# dial-a-hue.net
KiCad netlist of a schematic drawn in EAGLE
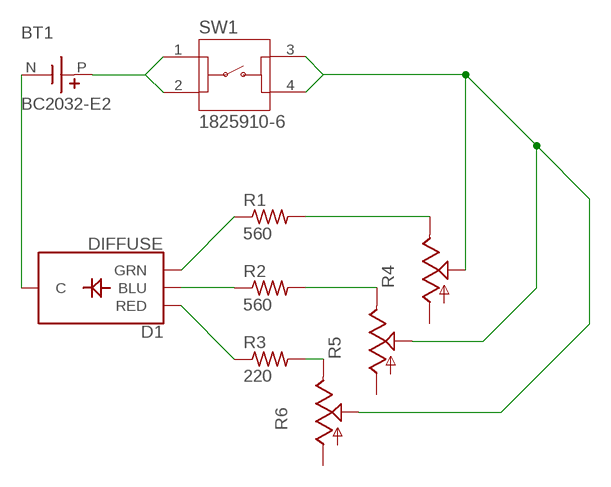
[diagram p0: schematic, sheet 1]

(export (version "E")
  (design (tool "Eeschema 10.0.6"))
  (components
    (comp (ref "BT1")
      (value "BC2032-E2")
      (footprint "eagle-import:MPD_BC2032-E2")
      (fields (field (name "DIGI-KEY_PART_NUMBER") "BC2032-E2-ND") (field (name "MF") "MPD _Memory"))
      (libsource (lib "eagle-import") (part "BC2032-E2"))
    )
    (comp (ref "D1")
      (value "DIFFUSE")
      (footprint "eagle-import:LED-RGB-THRU")
      (libsource (lib "eagle-import") (part "LED-RGB-CCDIFFUSE"))
    )
    (comp (ref "R1")
      (value "560")
      (footprint "eagle-import:0207_10")
      (libsource (lib "eagle-import") (part "R-US_0207/10"))
    )
    (comp (ref "R2")
      (value "560")
      (footprint "eagle-import:0207_10")
      (libsource (lib "eagle-import") (part "R-US_0207/10"))
    )
    (comp (ref "R3")
      (value "220")
      (footprint "eagle-import:0207_10")
      (libsource (lib "eagle-import") (part "R-US_0207/10"))
    )
    (comp (ref "R4")
      (value "TRIM_US-LI10")
      (footprint "eagle-import:LI10")
      (libsource (lib "eagle-import") (part "TRIM_US-LI10"))
    )
    (comp (ref "R5")
      (value "TRIM_US-LI10")
      (footprint "eagle-import:LI10")
      (libsource (lib "eagle-import") (part "TRIM_US-LI10"))
    )
    (comp (ref "R6")
      (value "TRIM_US-LI10")
      (footprint "eagle-import:LI10")
      (libsource (lib "eagle-import") (part "TRIM_US-LI10"))
    )
    (comp (ref "SW1")
      (value "1825910-6")
      (footprint "eagle-import:SW_1825910-6-4")
      (fields (field (name "DIGI-KEY_PART_NUMBER") "450-1650-ND") (field (name "MF") "TE Connectivity"))
      (libsource (lib "eagle-import") (part "1825910-6"))
    )
  )
  (nets
    (net (code "1") (name "Net-(BT1-PadP)") (class "Default")
      (node (ref "BT1") (pin "P") (pinfunction "P_P") (pintype "passive"))
      (node (ref "SW1") (pin "1") (pinfunction "1_1") (pintype "passive"))
      (node (ref "SW1") (pin "2") (pinfunction "2_2") (pintype "passive"))
    )
    (net (code "2") (name "Net-(D1-BLU)") (class "Default")
      (node (ref "D1") (pin "4") (pinfunction "BLU_4") (pintype "bidirectional"))
      (node (ref "R2") (pin "1") (pinfunction "1_1") (pintype "passive"))
    )
    (net (code "3") (name "Net-(D1-C)") (class "Default")
      (node (ref "BT1") (pin "N") (pinfunction "N_N") (pintype "passive"))
      (node (ref "D1") (pin "2") (pinfunction "C_2") (pintype "bidirectional"))
    )
    (net (code "4") (name "Net-(D1-GRN)") (class "Default")
      (node (ref "D1") (pin "3") (pinfunction "GRN_3") (pintype "bidirectional"))
      (node (ref "R1") (pin "1") (pinfunction "1_1") (pintype "passive"))
    )
    (net (code "5") (name "Net-(D1-RED)") (class "Default")
      (node (ref "D1") (pin "1") (pinfunction "RED_1") (pintype "bidirectional"))
      (node (ref "R3") (pin "1") (pinfunction "1_1") (pintype "passive"))
    )
    (net (code "6") (name "Net-(R1-Pad2)") (class "Default")
      (node (ref "R1") (pin "2") (pinfunction "2_2") (pintype "passive"))
      (node (ref "R4") (pin "E") (pinfunction "E_E") (pintype "passive"))
    )
    (net (code "7") (name "Net-(R2-Pad2)") (class "Default")
      (node (ref "R2") (pin "2") (pinfunction "2_2") (pintype "passive"))
      (node (ref "R5") (pin "E") (pinfunction "E_E") (pintype "passive"))
    )
    (net (code "8") (name "Net-(R3-Pad2)") (class "Default")
      (node (ref "R3") (pin "2") (pinfunction "2_2") (pintype "passive"))
      (node (ref "R6") (pin "E") (pinfunction "E_E") (pintype "passive"))
    )
    (net (code "9") (name "Net-(R4-PadS)") (class "Default")
      (node (ref "R4") (pin "S") (pinfunction "S_S") (pintype "passive"))
      (node (ref "R5") (pin "S") (pinfunction "S_S") (pintype "passive"))
      (node (ref "R6") (pin "S") (pinfunction "S_S") (pintype "passive"))
      (node (ref "SW1") (pin "3") (pinfunction "3_3") (pintype "passive"))
      (node (ref "SW1") (pin "4") (pinfunction "4_4") (pintype "passive"))
    )
    (net (code "10") (name "unconnected-(R4-PadA)") (class "Default")
      (node (ref "R4") (pin "A") (pinfunction "A_A") (pintype "passive"))
    )
    (net (code "11") (name "unconnected-(R5-PadA)") (class "Default")
      (node (ref "R5") (pin "A") (pinfunction "A_A") (pintype "passive"))
    )
    (net (code "12") (name "unconnected-(R6-PadA)") (class "Default")
      (node (ref "R6") (pin "A") (pinfunction "A_A") (pintype "passive"))
    )
  )
)
